# design.net
KiCad netlist of a schematic drawn in Altium Designer
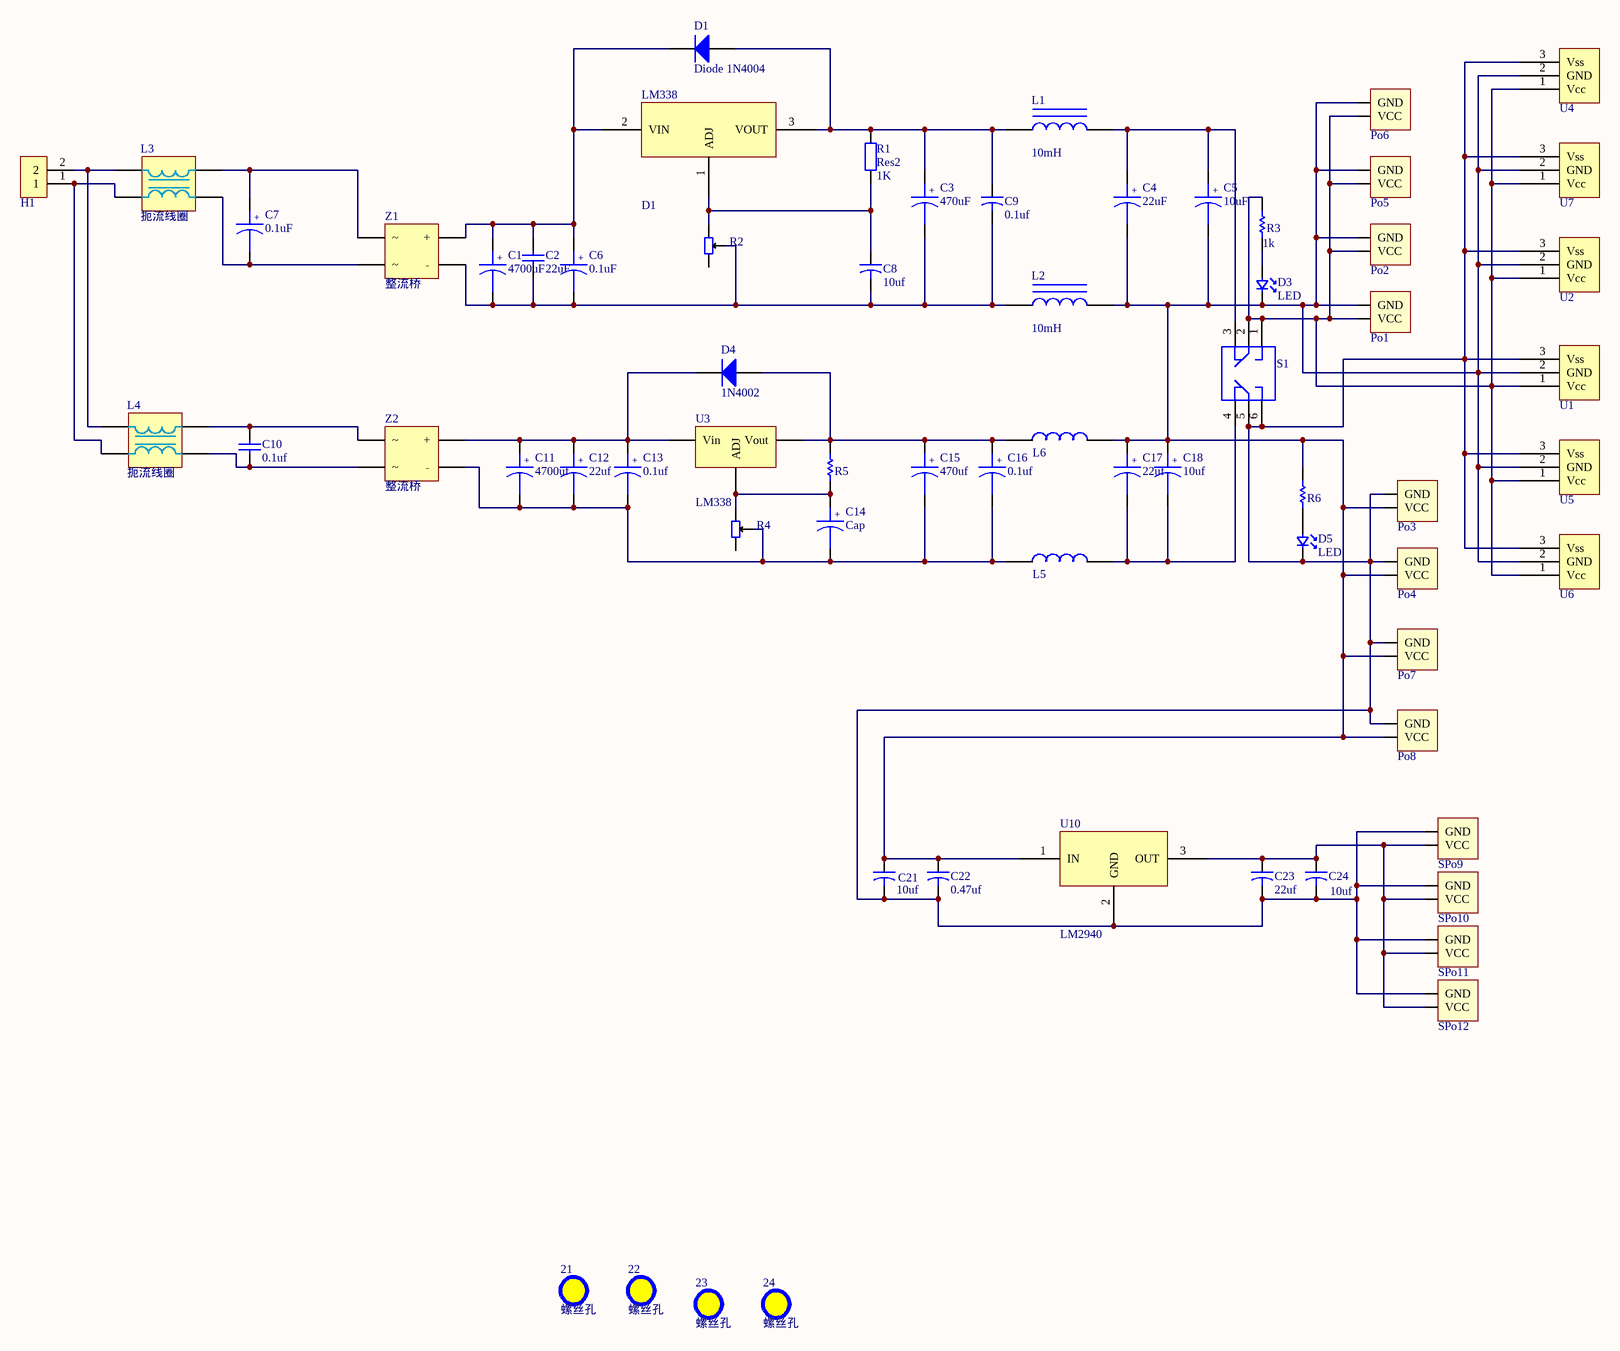
[diagram p0: 电源.SchDoc]

(export (version "E")
  (design (tool "Eeschema 10.0.6"))
  (components
    (comp (ref "21") (value "螺丝孔") (footprint "固定过孔") (libsource (lib "电源") (part "螺丝孔")))
    (comp (ref "22") (value "螺丝孔") (footprint "固定过孔") (libsource (lib "电源") (part "螺丝孔")))
    (comp (ref "23") (value "螺丝孔") (footprint "固定过孔") (libsource (lib "电源") (part "螺丝孔")))
    (comp (ref "24") (value "螺丝孔") (footprint "固定过孔") (libsource (lib "电源") (part "螺丝孔")))
    (comp (ref "C1") (value "4700uF") (footprint "4700UF_50V") (libsource (lib "电源") (part "Cap")))
    (comp (ref "C2")
      (value "22uF")
      (footprint "22UF_50V")
      (description "Capacitor")
      (fields (field (name "PUBLISHER") "Altium Limited"))
      (libsource (lib "Miscellaneous Devices") (part "Cap"))
    )
    (comp (ref "C3") (value "470uF") (footprint "C DIP DIA6.3") (libsource (lib "电源") (part "Cap")))
    (comp (ref "C4") (value "22uF") (footprint "22UF_50V") (libsource (lib "电源") (part "Cap")))
    (comp (ref "C5") (value "10uF") (footprint "陶瓷电容") (libsource (lib "电源") (part "Cap")))
    (comp (ref "C6") (value "0.1uF") (footprint "独石电容") (libsource (lib "电源") (part "Cap")))
    (comp (ref "C7") (value "0.1uF") (footprint "安规电容") (libsource (lib "电源") (part "Cap")))
    (comp (ref "C8")
      (value "Cap")
      (footprint "陶瓷电容")
      (fields (field (name "值") "10uf"))
      (libsource (lib "电源") (part "Cap_1"))
    )
    (comp (ref "C9")
      (value "Cap")
      (footprint "陶瓷电容")
      (fields (field (name "值") "0.1uf"))
      (libsource (lib "电源") (part "Cap_1"))
    )
    (comp (ref "C10")
      (value "Cap1")
      (footprint "安规电容")
      (fields (field (name "值") "0.1uf"))
      (libsource (lib "电源") (part "Cap1"))
    )
    (comp (ref "C11") (value "4700uf") (footprint "4700UF_50V") (libsource (lib "电源") (part "Cap")))
    (comp (ref "C12") (value "22uf") (footprint "22UF_50V") (libsource (lib "电源") (part "Cap")))
    (comp (ref "C13") (value "0.1uf") (footprint "独石电容") (libsource (lib "电源") (part "Cap")))
    (comp (ref "C14") (value "Cap") (footprint "陶瓷电容") (libsource (lib "电源") (part "Cap")))
    (comp (ref "C15") (value "470uf") (footprint "C DIP DIA6.3") (libsource (lib "电源") (part "Cap")))
    (comp (ref "C16") (value "0.1uf") (footprint "陶瓷电容") (libsource (lib "电源") (part "Cap")))
    (comp (ref "C17") (value "22uf") (footprint "22UF_50V") (libsource (lib "电源") (part "Cap")))
    (comp (ref "C18") (value "10uf") (footprint "陶瓷电容") (libsource (lib "电源") (part "Cap")))
    (comp (ref "C21")
      (value "Cap")
      (footprint "陶瓷电容")
      (fields (field (name "值") "10uf"))
      (libsource (lib "电源") (part "Cap_1"))
    )
    (comp (ref "C22")
      (value "Cap")
      (footprint "陶瓷电容")
      (fields (field (name "值") "0.47uf"))
      (libsource (lib "电源") (part "Cap_1"))
    )
    (comp (ref "C23")
      (value "Cap")
      (footprint "22UF_50V")
      (fields (field (name "值") "22uf"))
      (libsource (lib "电源") (part "Cap_1"))
    )
    (comp (ref "C24")
      (value "Cap")
      (footprint "陶瓷电容")
      (fields (field (name "值") "10uf"))
      (libsource (lib "电源") (part "Cap_1"))
    )
    (comp (ref "D1")
      (value "Diode 1N4004")
      (footprint "SMC")
      (description "1 Amp General Purpose Rectifier")
      (fields (field (name "PUBLISHER") "Altium Limited"))
      (libsource (lib "Miscellaneous Devices") (part "Diode 1N4004"))
    )
    (comp (ref "D3") (value "LED") (footprint "0805_s") (libsource (lib "电源") (part "LED")))
    (comp (ref "D4")
      (value "1N4002")
      (footprint "SMC")
      (description "Default Diode")
      (fields (field (name "PUBLISHER") "Altium Limited"))
      (libsource (lib "电源") (part "Diode"))
    )
    (comp (ref "D5") (value "LED") (footprint "0805_s") (libsource (lib "电源") (part "LED")))
    (comp (ref "H1") (value "HT3.96-2P") (footprint "HT39.6-2P-S") (libsource (lib "电源") (part "HT3.96-2P")))
    (comp (ref "L1")
      (value "10mH")
      (footprint "功率电感-12x12 - duplicate")
      (description "Magnetic-Core Inductor")
      (fields (field (name "Comment") "Inductor Iron") (field (name "PUBLISHER") "Altium Limited"))
      (libsource (lib "Miscellaneous Devices") (part "Inductor Iron"))
    )
    (comp (ref "L2")
      (value "10mH")
      (footprint "功率电感-12x12 - duplicate")
      (description "Magnetic-Core Inductor")
      (fields (field (name "Comment") "Inductor Iron") (field (name "PUBLISHER") "Altium Limited"))
      (libsource (lib "Miscellaneous Devices") (part "Inductor Iron"))
    )
    (comp (ref "L3") (value "扼流线圈") (footprint "扼流线圈") (libsource (lib "电源") (part "扼流线圈")))
    (comp (ref "L4") (value "扼流线圈") (footprint "扼流线圈") (libsource (lib "电源") (part "扼流线圈")))
    (comp (ref "L5") (value "SMD") (footprint "功率电感-12x12 - duplicate") (libsource (lib "电源") (part "功率电感")))
    (comp (ref "L6") (value "SMD") (footprint "功率电感-12x12 - duplicate") (libsource (lib "电源") (part "功率电感")))
    (comp (ref "LM338") (value "D1") (footprint "LM338") (libsource (lib "电源") (part "LM338")))
    (comp (ref "Po1")
      (value "Power_2Port")
      (footprint "Power_S_2Port")
      (libsource (lib "电源") (part "Power_2Port"))
    )
    (comp (ref "Po2")
      (value "Power_2Port")
      (footprint "Power_S_2Port")
      (libsource (lib "电源") (part "Power_2Port"))
    )
    (comp (ref "Po3")
      (value "Power_2Port")
      (footprint "Power_S_2Port")
      (libsource (lib "电源") (part "Power_2Port"))
    )
    (comp (ref "Po4")
      (value "Power_2Port")
      (footprint "Power_S_2Port")
      (libsource (lib "电源") (part "Power_2Port"))
    )
    (comp (ref "Po5")
      (value "Power_2Port")
      (footprint "Power_S_2Port")
      (libsource (lib "电源") (part "Power_2Port"))
    )
    (comp (ref "Po6")
      (value "Power_2Port")
      (footprint "Power_S_2Port")
      (libsource (lib "电源") (part "Power_2Port"))
    )
    (comp (ref "Po7")
      (value "Power_2Port")
      (footprint "Power_S_2Port")
      (libsource (lib "电源") (part "Power_2Port"))
    )
    (comp (ref "Po8")
      (value "Power_2Port")
      (footprint "Power_S_2Port")
      (libsource (lib "电源") (part "Power_2Port"))
    )
    (comp (ref "R1")
      (value "Res2")
      (footprint "0805")
      (description "Resistor")
      (fields (field (name "ALTIUM_VALUE") "1K") (field (name "PUBLISHER") "Altium Limited"))
      (libsource (lib "Miscellaneous Devices") (part "Res2"))
    )
    (comp (ref "R2") (value "可调电位器1") (footprint "电位器") (libsource (lib "电源") (part "可调电位器1")))
    (comp (ref "R3") (value "1k") (footprint "0805") (description "1K") (libsource (lib "电源") (part "RES")))
    (comp (ref "R4") (value "可调电位器1") (footprint "电位器") (libsource (lib "电源") (part "可调电位器1")))
    (comp (ref "R5") (value "RES") (footprint "0805") (libsource (lib "电源") (part "RES")))
    (comp (ref "R6") (value "RES") (footprint "0805") (libsource (lib "电源") (part "RES")))
    (comp (ref "S1") (value "双掷开关") (footprint "SWITCH") (libsource (lib "电源") (part "双掷开关")))
    (comp (ref "SPo9")
      (value "Power_2Port")
      (footprint "Power_S_2Port")
      (libsource (lib "电源") (part "Power_2Port"))
    )
    (comp (ref "SPo10")
      (value "Power_2Port")
      (footprint "Power_S_2Port")
      (libsource (lib "电源") (part "Power_2Port"))
    )
    (comp (ref "SPo11")
      (value "Power_2Port")
      (footprint "Power_S_2Port")
      (libsource (lib "电源") (part "Power_2Port"))
    )
    (comp (ref "SPo12")
      (value "Power_2Port")
      (footprint "Power_S_2Port")
      (libsource (lib "电源") (part "Power_2Port"))
    )
    (comp (ref "U1") (value "XH2.54-3p") (footprint "XH2.54-3p") (libsource (lib "电源") (part "XH2.54-3p")))
    (comp (ref "U2") (value "XH2.54-3p") (footprint "XH2.54-3p") (libsource (lib "电源") (part "XH2.54-3p")))
    (comp (ref "U3") (value "LM338") (footprint "LM338") (libsource (lib "电源") (part "LM338_1")))
    (comp (ref "U4") (value "XH2.54-3p") (footprint "XH2.54-3p") (libsource (lib "电源") (part "XH2.54-3p")))
    (comp (ref "U5") (value "XH2.54-3p") (footprint "XH2.54-3p") (libsource (lib "电源") (part "XH2.54-3p")))
    (comp (ref "U6") (value "XH2.54-3p") (footprint "XH2.54-3p") (libsource (lib "电源") (part "XH2.54-3p")))
    (comp (ref "U7") (value "XH2.54-3p") (footprint "XH2.54-3p") (libsource (lib "电源") (part "XH2.54-3p")))
    (comp (ref "U10") (value "LM2940") (footprint "TO-220") (libsource (lib "电源") (part "LM2940")))
    (comp (ref "Z1") (value "整流桥") (footprint "整流桥") (libsource (lib "电源") (part "整流桥")))
    (comp (ref "Z2") (value "整流桥") (footprint "整流桥") (libsource (lib "电源") (part "整流桥")))
  )
  (nets
    (net (code "1") (name "Net-(C4-Pad1)") (class "Default")
      (node (ref "C4") (pin "1") (pinfunction "1_1") (pintype "passive"))
      (node (ref "C5") (pin "1") (pinfunction "1_1") (pintype "passive"))
      (node (ref "L1") (pin "2") (pinfunction "2_2") (pintype "passive"))
      (node (ref "S1") (pin "3") (pinfunction "3_3") (pintype "passive"))
    )
    (net (code "2") (name "Net-(C7-Pad1)") (class "Default")
      (node (ref "C7") (pin "1") (pinfunction "1_1") (pintype "passive"))
      (node (ref "L3") (pin "2") (pinfunction "2_2") (pintype "passive"))
      (node (ref "Z1") (pin "2") (pinfunction "~_2") (pintype "passive"))
    )
    (net (code "3") (name "Net-(C7-Pad2)") (class "Default")
      (node (ref "C7") (pin "2") (pinfunction "2_2") (pintype "passive"))
      (node (ref "L3") (pin "3") (pinfunction "3_3") (pintype "passive"))
      (node (ref "Z1") (pin "3") (pinfunction "~_3") (pintype "passive"))
    )
    (net (code "4") (name "Net-(C10-Pad1)") (class "Default")
      (node (ref "C10") (pin "1") (pinfunction "1_1") (pintype "passive"))
      (node (ref "L4") (pin "3") (pinfunction "3_3") (pintype "passive"))
      (node (ref "Z2") (pin "3") (pinfunction "~_3") (pintype "passive"))
    )
    (net (code "5") (name "Net-(C10-Pad2)") (class "Default")
      (node (ref "C10") (pin "2") (pinfunction "2_2") (pintype "passive"))
      (node (ref "L4") (pin "2") (pinfunction "2_2") (pintype "passive"))
      (node (ref "Z2") (pin "2") (pinfunction "~_2") (pintype "passive"))
    )
    (net (code "6") (name "Net-(C17-Pad2)") (class "Default")
      (node (ref "C17") (pin "2") (pinfunction "2_2") (pintype "passive"))
      (node (ref "C18") (pin "2") (pinfunction "2_2") (pintype "passive"))
      (node (ref "L5") (pin "2") (pintype "passive"))
      (node (ref "S1") (pin "4") (pinfunction "4_4") (pintype "passive"))
    )
    (net (code "7") (name "Net-(D1-A)") (class "Default")
      (node (ref "C3") (pin "1") (pinfunction "1_1") (pintype "passive"))
      (node (ref "C9") (pin "1") (pinfunction "1_1") (pintype "passive"))
      (node (ref "D1") (pin "1") (pinfunction "A_1") (pintype "passive"))
      (node (ref "L1") (pin "1") (pinfunction "1_1") (pintype "passive"))
      (node (ref "LM338") (pin "3") (pinfunction "VOUT_3") (pintype "passive"))
      (node (ref "R1") (pin "2") (pinfunction "2_2") (pintype "passive"))
    )
    (net (code "8") (name "Net-(D1-K)") (class "Default")
      (node (ref "C1") (pin "1") (pinfunction "1_1") (pintype "passive"))
      (node (ref "C2") (pin "2") (pinfunction "2_2") (pintype "passive"))
      (node (ref "C6") (pin "1") (pinfunction "1_1") (pintype "passive"))
      (node (ref "D1") (pin "2") (pinfunction "K_2") (pintype "passive"))
      (node (ref "LM338") (pin "2") (pinfunction "VIN_2") (pintype "passive"))
      (node (ref "Z1") (pin "1") (pinfunction "+_1") (pintype "passive"))
    )
    (net (code "9") (name "Net-(D3-Pad2)") (class "Default")
      (node (ref "D3") (pin "2") (pinfunction "2_2") (pintype "passive"))
      (node (ref "R3") (pin "1") (pinfunction "1_1") (pintype "passive"))
    )
    (net (code "10") (name "Net-(D4-A)") (class "Default")
      (node (ref "C15") (pin "1") (pinfunction "1_1") (pintype "passive"))
      (node (ref "C16") (pin "1") (pinfunction "1_1") (pintype "passive"))
      (node (ref "D4") (pin "1") (pinfunction "A_1") (pintype "passive"))
      (node (ref "L6") (pin "1") (pintype "passive"))
      (node (ref "R5") (pin "2") (pinfunction "2_2") (pintype "passive"))
      (node (ref "U3") (pin "3") (pinfunction "Vout_3") (pintype "passive"))
    )
    (net (code "11") (name "Net-(D4-K)") (class "Default")
      (node (ref "C11") (pin "1") (pinfunction "1_1") (pintype "passive"))
      (node (ref "C12") (pin "1") (pinfunction "1_1") (pintype "passive"))
      (node (ref "C13") (pin "1") (pinfunction "1_1") (pintype "passive"))
      (node (ref "D4") (pin "2") (pinfunction "K_2") (pintype "passive"))
      (node (ref "U3") (pin "1") (pinfunction "Vin_1") (pintype "passive"))
      (node (ref "Z2") (pin "1") (pinfunction "+_1") (pintype "passive"))
    )
    (net (code "12") (name "Net-(D5-Pad2)") (class "Default")
      (node (ref "D5") (pin "2") (pinfunction "2_2") (pintype "passive"))
      (node (ref "R6") (pin "1") (pinfunction "1_1") (pintype "passive"))
    )
    (net (code "13") (name "Net-(H1-Pad1)") (class "Default")
      (node (ref "H1") (pin "1") (pinfunction "1_1") (pintype "passive"))
      (node (ref "L3") (pin "4") (pinfunction "4_4") (pintype "passive"))
      (node (ref "L4") (pin "4") (pinfunction "4_4") (pintype "passive"))
    )
    (net (code "14") (name "Net-(H1-Pad2)") (class "Default")
      (node (ref "H1") (pin "2") (pinfunction "2_2") (pintype "passive"))
      (node (ref "L3") (pin "1") (pinfunction "1_1") (pintype "passive"))
      (node (ref "L4") (pin "1") (pinfunction "1_1") (pintype "passive"))
    )
    (net (code "15") (name "Net-(LM338-ADJ)") (class "Default")
      (node (ref "C8") (pin "1") (pinfunction "1_1") (pintype "passive"))
      (node (ref "LM338") (pin "1") (pinfunction "ADJ_1") (pintype "passive"))
      (node (ref "R1") (pin "1") (pinfunction "1_1") (pintype "passive"))
      (node (ref "R2") (pin "3") (pinfunction "3_3") (pintype "passive"))
    )
    (net (code "16") (name "Net-(Po1-GND)") (class "Default")
      (node (ref "C17") (pin "1") (pinfunction "1_1") (pintype "passive"))
      (node (ref "C18") (pin "1") (pinfunction "1_1") (pintype "passive"))
      (node (ref "C21") (pin "1") (pinfunction "1_1") (pintype "passive"))
      (node (ref "C22") (pin "1") (pinfunction "1_1") (pintype "passive"))
      (node (ref "C4") (pin "2") (pinfunction "2_2") (pintype "passive"))
      (node (ref "C5") (pin "2") (pinfunction "2_2") (pintype "passive"))
      (node (ref "D3") (pin "1") (pinfunction "1_1") (pintype "passive"))
      (node (ref "L2") (pin "2") (pinfunction "2_2") (pintype "passive"))
      (node (ref "L6") (pin "2") (pintype "passive"))
      (node (ref "Po1") (pin "2") (pinfunction "GND_2") (pintype "passive"))
      (node (ref "Po2") (pin "2") (pinfunction "GND_2") (pintype "passive"))
      (node (ref "Po3") (pin "1") (pinfunction "VCC_1") (pintype "passive"))
      (node (ref "Po4") (pin "1") (pinfunction "VCC_1") (pintype "passive"))
      (node (ref "Po5") (pin "2") (pinfunction "GND_2") (pintype "passive"))
      (node (ref "Po6") (pin "2") (pinfunction "GND_2") (pintype "passive"))
      (node (ref "Po7") (pin "1") (pinfunction "VCC_1") (pintype "passive"))
      (node (ref "Po8") (pin "1") (pinfunction "VCC_1") (pintype "passive"))
      (node (ref "R6") (pin "2") (pinfunction "2_2") (pintype "passive"))
      (node (ref "U1") (pin "2") (pinfunction "GND_2") (pintype "passive"))
      (node (ref "U10") (pin "1") (pinfunction "IN_1") (pintype "passive"))
      (node (ref "U2") (pin "2") (pinfunction "GND_2") (pintype "passive"))
      (node (ref "U4") (pin "2") (pinfunction "GND_2") (pintype "passive"))
      (node (ref "U5") (pin "2") (pinfunction "GND_2") (pintype "passive"))
      (node (ref "U6") (pin "2") (pinfunction "GND_2") (pintype "passive"))
      (node (ref "U7") (pin "2") (pinfunction "GND_2") (pintype "passive"))
    )
    (net (code "17") (name "Net-(Po1-VCC)") (class "Default")
      (node (ref "Po1") (pin "1") (pinfunction "VCC_1") (pintype "passive"))
      (node (ref "Po2") (pin "1") (pinfunction "VCC_1") (pintype "passive"))
      (node (ref "Po5") (pin "1") (pinfunction "VCC_1") (pintype "passive"))
      (node (ref "Po6") (pin "1") (pinfunction "VCC_1") (pintype "passive"))
      (node (ref "R3") (pin "2") (pinfunction "2_2") (pintype "passive"))
      (node (ref "S1") (pin "1") (pinfunction "1_1") (pintype "passive"))
      (node (ref "S1") (pin "2") (pinfunction "2_2") (pintype "passive"))
      (node (ref "U1") (pin "1") (pinfunction "Vcc_1") (pintype "passive"))
      (node (ref "U2") (pin "1") (pinfunction "Vcc_1") (pintype "passive"))
      (node (ref "U4") (pin "1") (pinfunction "Vcc_1") (pintype "passive"))
      (node (ref "U5") (pin "1") (pinfunction "Vcc_1") (pintype "passive"))
      (node (ref "U6") (pin "1") (pinfunction "Vcc_1") (pintype "passive"))
      (node (ref "U7") (pin "1") (pinfunction "Vcc_1") (pintype "passive"))
    )
    (net (code "18") (name "Net-(Po3-GND)") (class "Default")
      (node (ref "C21") (pin "2") (pinfunction "2_2") (pintype "passive"))
      (node (ref "C22") (pin "2") (pinfunction "2_2") (pintype "passive"))
      (node (ref "C23") (pin "2") (pinfunction "2_2") (pintype "passive"))
      (node (ref "C24") (pin "2") (pinfunction "2_2") (pintype "passive"))
      (node (ref "D5") (pin "1") (pinfunction "1_1") (pintype "passive"))
      (node (ref "Po3") (pin "2") (pinfunction "GND_2") (pintype "passive"))
      (node (ref "Po4") (pin "2") (pinfunction "GND_2") (pintype "passive"))
      (node (ref "Po7") (pin "2") (pinfunction "GND_2") (pintype "passive"))
      (node (ref "Po8") (pin "2") (pinfunction "GND_2") (pintype "passive"))
      (node (ref "S1") (pin "5") (pinfunction "5_5") (pintype "passive"))
      (node (ref "S1") (pin "6") (pinfunction "6_6") (pintype "passive"))
      (node (ref "SPo10") (pin "2") (pinfunction "GND_2") (pintype "passive"))
      (node (ref "SPo11") (pin "2") (pinfunction "GND_2") (pintype "passive"))
      (node (ref "SPo12") (pin "2") (pinfunction "GND_2") (pintype "passive"))
      (node (ref "SPo9") (pin "2") (pinfunction "GND_2") (pintype "passive"))
      (node (ref "U1") (pin "3") (pinfunction "Vss_3") (pintype "passive"))
      (node (ref "U10") (pin "2") (pinfunction "GND_2") (pintype "passive"))
      (node (ref "U2") (pin "3") (pinfunction "Vss_3") (pintype "passive"))
      (node (ref "U4") (pin "3") (pinfunction "Vss_3") (pintype "passive"))
      (node (ref "U5") (pin "3") (pinfunction "Vss_3") (pintype "passive"))
      (node (ref "U6") (pin "3") (pinfunction "Vss_3") (pintype "passive"))
      (node (ref "U7") (pin "3") (pinfunction "Vss_3") (pintype "passive"))
    )
    (net (code "19") (name "Net-(SPo10-VCC)") (class "Default")
      (node (ref "C23") (pin "1") (pinfunction "1_1") (pintype "passive"))
      (node (ref "C24") (pin "1") (pinfunction "1_1") (pintype "passive"))
      (node (ref "SPo10") (pin "1") (pinfunction "VCC_1") (pintype "passive"))
      (node (ref "SPo11") (pin "1") (pinfunction "VCC_1") (pintype "passive"))
      (node (ref "SPo12") (pin "1") (pinfunction "VCC_1") (pintype "passive"))
      (node (ref "SPo9") (pin "1") (pinfunction "VCC_1") (pintype "passive"))
      (node (ref "U10") (pin "3") (pinfunction "OUT_3") (pintype "passive"))
    )
    (net (code "20") (name "Net-(U3-ADJ)") (class "Default")
      (node (ref "C14") (pin "1") (pinfunction "1_1") (pintype "passive"))
      (node (ref "R4") (pin "3") (pinfunction "3_3") (pintype "passive"))
      (node (ref "R5") (pin "1") (pinfunction "1_1") (pintype "passive"))
      (node (ref "U3") (pin "2") (pinfunction "ADJ_2") (pintype "passive"))
    )
    (net (code "21") (name "Net-(Z1-﹣)") (class "Default")
      (node (ref "C1") (pin "2") (pinfunction "2_2") (pintype "passive"))
      (node (ref "C2") (pin "1") (pinfunction "1_1") (pintype "passive"))
      (node (ref "C3") (pin "2") (pinfunction "2_2") (pintype "passive"))
      (node (ref "C6") (pin "2") (pinfunction "2_2") (pintype "passive"))
      (node (ref "C8") (pin "2") (pinfunction "2_2") (pintype "passive"))
      (node (ref "C9") (pin "2") (pinfunction "2_2") (pintype "passive"))
      (node (ref "L2") (pin "1") (pinfunction "1_1") (pintype "passive"))
      (node (ref "R2") (pin "2") (pinfunction "2_2") (pintype "passive"))
      (node (ref "Z1") (pin "4") (pinfunction "﹣_4") (pintype "passive"))
    )
    (net (code "22") (name "Net-(Z2-﹣)") (class "Default")
      (node (ref "C11") (pin "2") (pinfunction "2_2") (pintype "passive"))
      (node (ref "C12") (pin "2") (pinfunction "2_2") (pintype "passive"))
      (node (ref "C13") (pin "2") (pinfunction "2_2") (pintype "passive"))
      (node (ref "C14") (pin "2") (pinfunction "2_2") (pintype "passive"))
      (node (ref "C15") (pin "2") (pinfunction "2_2") (pintype "passive"))
      (node (ref "C16") (pin "2") (pinfunction "2_2") (pintype "passive"))
      (node (ref "L5") (pin "1") (pintype "passive"))
      (node (ref "R4") (pin "2") (pinfunction "2_2") (pintype "passive"))
      (node (ref "Z2") (pin "4") (pinfunction "﹣_4") (pintype "passive"))
    )
    (net (code "23") (name "unconnected-(R2-Pad1)") (class "Default")
      (node (ref "R2") (pin "1") (pinfunction "1_1") (pintype "passive"))
    )
    (net (code "24") (name "unconnected-(R4-Pad1)") (class "Default")
      (node (ref "R4") (pin "1") (pinfunction "1_1") (pintype "passive"))
    )
  )
)
